# ROV_Power_V2_0.net
KiCad netlist of a schematic drawn in Altium Designer
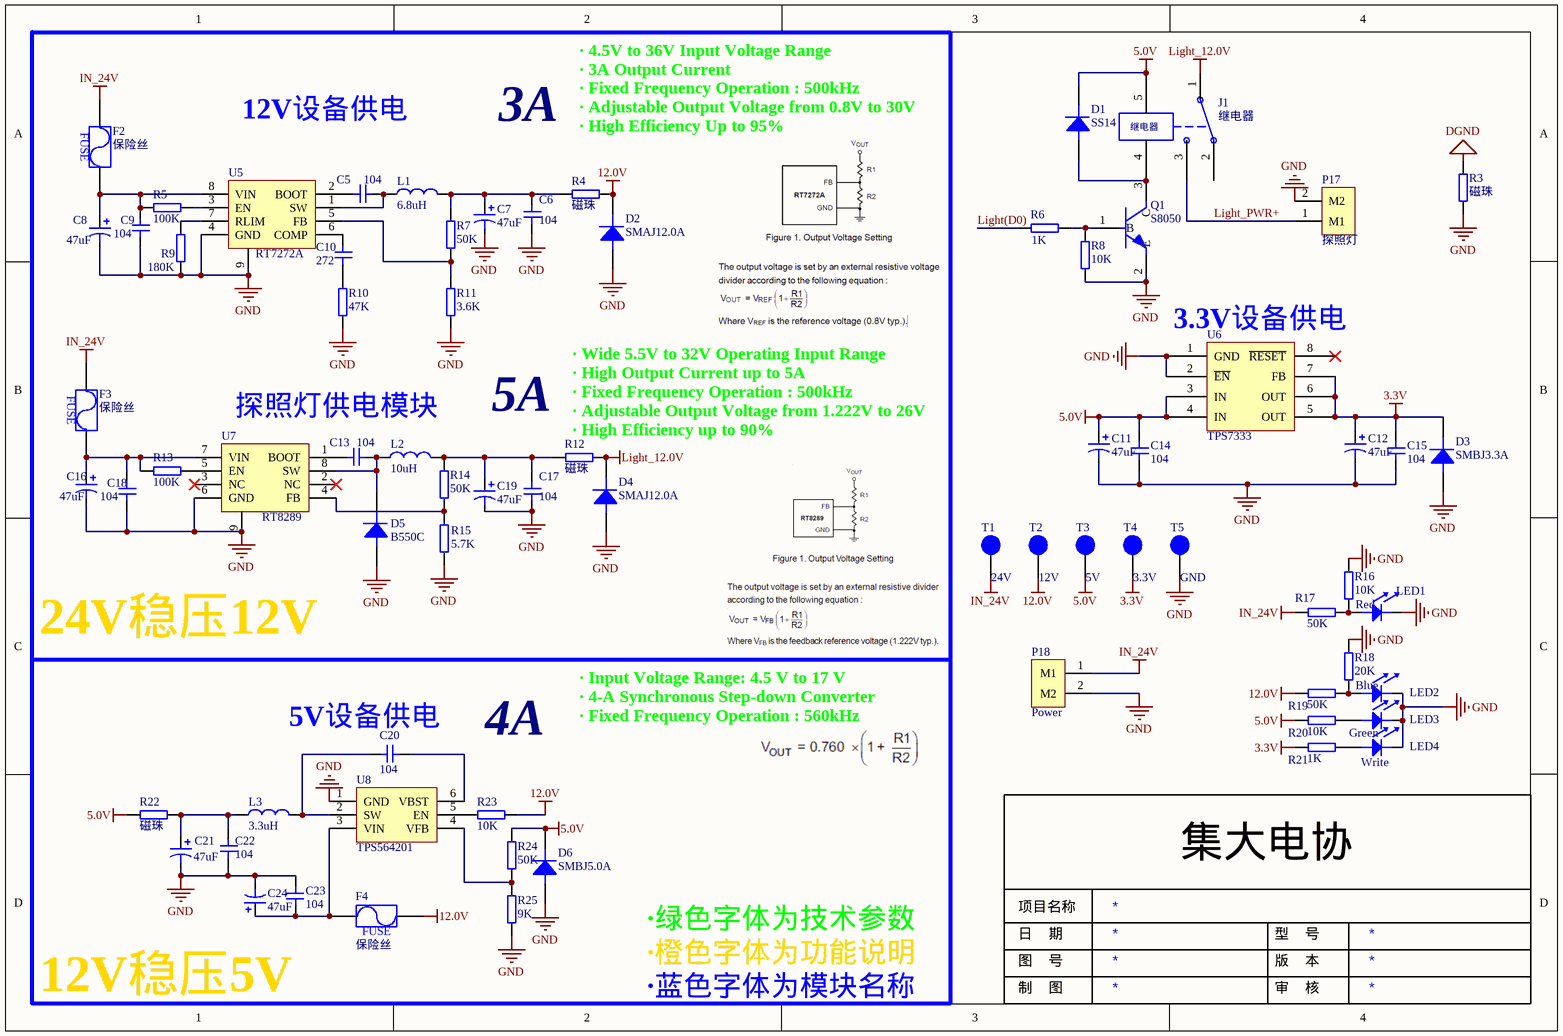
[diagram p0: ROV_Power V2.0.SchDoc]

(export (version "E")
  (design (tool "Eeschema 10.0.6"))
  (components
    (comp (ref "C5")
      (value "104")
      (footprint "0805C")
      (description "无极贴片电容")
      (libsource (lib "集大电协1.2") (part "Cap1"))
    )
    (comp (ref "C6")
      (value "104")
      (footprint "0805C")
      (description "无极贴片电容")
      (libsource (lib "集大电协1.2") (part "Cap1"))
    )
    (comp (ref "C7")
      (value "47uF")
      (footprint "TAJ-B")
      (description "极性贴片电容")
      (libsource (lib "集大电协1.2") (part "Pol Cap"))
    )
    (comp (ref "C8")
      (value "47uF")
      (footprint "TAJ-B")
      (description "极性贴片电容")
      (libsource (lib "集大电协1.2") (part "Pol Cap"))
    )
    (comp (ref "C9")
      (value "104")
      (footprint "0805C")
      (description "无极贴片电容")
      (libsource (lib "集大电协1.2") (part "Cap1"))
    )
    (comp (ref "C10")
      (value "272")
      (footprint "0805C")
      (description "无极贴片电容")
      (libsource (lib "集大电协1.2") (part "Cap1"))
    )
    (comp (ref "C11")
      (value "47uF")
      (footprint "TAJ-B")
      (description "极性贴片电容")
      (libsource (lib "集大电协1.2") (part "Pol Cap"))
    )
    (comp (ref "C12")
      (value "47uF")
      (footprint "TAJ-B")
      (description "极性贴片电容")
      (libsource (lib "集大电协1.2") (part "Pol Cap"))
    )
    (comp (ref "C13")
      (value "104")
      (footprint "0805C")
      (description "无极贴片电容")
      (libsource (lib "集大电协1.2") (part "Cap1"))
    )
    (comp (ref "C14")
      (value "104")
      (footprint "0805C")
      (description "无极贴片电容")
      (libsource (lib "集大电协1.2") (part "Cap1"))
    )
    (comp (ref "C15")
      (value "104")
      (footprint "0805C")
      (description "无极贴片电容")
      (libsource (lib "集大电协1.2") (part "Cap1"))
    )
    (comp (ref "C16")
      (value "47uF")
      (footprint "TAJ-B")
      (description "极性贴片电容")
      (libsource (lib "集大电协1.2") (part "Pol Cap"))
    )
    (comp (ref "C17")
      (value "104")
      (footprint "0805C")
      (description "无极贴片电容")
      (libsource (lib "集大电协1.2") (part "Cap1"))
    )
    (comp (ref "C18")
      (value "104")
      (footprint "0805C")
      (description "无极贴片电容")
      (libsource (lib "集大电协1.2") (part "Cap1"))
    )
    (comp (ref "C19")
      (value "47uF")
      (footprint "TAJ-B")
      (description "极性贴片电容")
      (libsource (lib "集大电协1.2") (part "Pol Cap"))
    )
    (comp (ref "C20")
      (value "104")
      (footprint "0805C")
      (description "无极贴片电容")
      (libsource (lib "集大电协1.2") (part "Cap1"))
    )
    (comp (ref "C21")
      (value "47uF")
      (footprint "TAJ-B")
      (description "极性贴片电容")
      (libsource (lib "集大电协1.2") (part "Pol Cap"))
    )
    (comp (ref "C22")
      (value "104")
      (footprint "0805C")
      (description "无极贴片电容")
      (libsource (lib "集大电协1.2") (part "Cap1"))
    )
    (comp (ref "C23")
      (value "104")
      (footprint "0805C")
      (description "无极贴片电容")
      (libsource (lib "集大电协1.2") (part "Cap1"))
    )
    (comp (ref "C24")
      (value "47uF")
      (footprint "TAJ-B")
      (description "极性贴片电容")
      (libsource (lib "集大电协1.2") (part "Pol Cap"))
    )
    (comp (ref "D1")
      (value "SS14")
      (footprint "SMA/DO-214AC")
      (description "二极管")
      (libsource (lib "集大电协1.1.0") (part "Diode"))
    )
    (comp (ref "D2")
      (value "SMAJ12.0A")
      (footprint "SMBJ")
      (description "二极管")
      (libsource (lib "集大电协1.2") (part "Diode"))
    )
    (comp (ref "D3")
      (value "SMBJ3.3A")
      (footprint "SMBJ")
      (description "二极管")
      (libsource (lib "集大电协1.2") (part "Diode"))
    )
    (comp (ref "D4")
      (value "SMAJ12.0A")
      (footprint "SMBJ")
      (description "二极管")
      (libsource (lib "集大电协1.2") (part "Diode"))
    )
    (comp (ref "D5")
      (value "B550C")
      (footprint "SMBJ")
      (description "二极管")
      (libsource (lib "集大电协1.2") (part "Diode"))
    )
    (comp (ref "D6")
      (value "SMBJ5.0A")
      (footprint "SMBJ")
      (description "二极管")
      (libsource (lib "集大电协1.2") (part "Diode"))
    )
    (comp (ref "F2") (value "保险丝") (footprint "1812") (libsource (lib "集大电协1.2") (part "Fuse")))
    (comp (ref "F3") (value "保险丝") (footprint "1812") (libsource (lib "集大电协1.2") (part "Fuse")))
    (comp (ref "F4") (value "保险丝") (footprint "1812") (libsource (lib "集大电协1.2") (part "Fuse")))
    (comp (ref "J1") (value "继电器") (footprint "继电器(小型)") (libsource (lib "集大电协1.1.0") (part "继电器")))
    (comp (ref "L1")
      (value "6.8uH")
      (footprint "电感")
      (description "电感")
      (libsource (lib "集大电协1.2") (part "L"))
    )
    (comp (ref "L2")
      (value "10uH")
      (footprint "电感")
      (description "电感")
      (libsource (lib "集大电协1.2") (part "L"))
    )
    (comp (ref "L3")
      (value "3.3uH")
      (footprint "电感")
      (description "电感")
      (libsource (lib "集大电协1.2") (part "L"))
    )
    (comp (ref "LED1")
      (value "Red")
      (footprint "0805LED(GREEN)")
      (description "发光二极管")
      (libsource (lib "集大电协1.2") (part "LED"))
    )
    (comp (ref "LED2")
      (value "Blue")
      (footprint "0805LED(RED)")
      (description "发光二极管")
      (libsource (lib "集大电协1.2") (part "LED"))
    )
    (comp (ref "LED3")
      (value "Green")
      (footprint "0805LED(RED)")
      (description "发光二极管")
      (libsource (lib "集大电协1.2") (part "LED"))
    )
    (comp (ref "LED4")
      (value "Write")
      (footprint "0805LED(RED)")
      (description "发光二极管")
      (libsource (lib "集大电协1.2") (part "LED"))
    )
    (comp (ref "P17")
      (value "探照灯")
      (footprint "KF128-2P")
      (description "2PIN")
      (libsource (lib "集大电协1.2") (part "接线端子-2PIN"))
    )
    (comp (ref "P18")
      (value "Power")
      (footprint "XT60-F")
      (description "2PIN")
      (libsource (lib "") (part "接线端子-2PIN_1"))
    )
    (comp (ref "Q1")
      (value "S8050")
      (footprint "SOT-23")
      (description "NPN三极管")
      (libsource (lib "集大电协1.1.0") (part "NPN"))
    )
    (comp (ref "R3")
      (value "磁珠")
      (footprint "1210R")
      (description "电阻")
      (libsource (lib "集大电协1.2") (part "Res"))
    )
    (comp (ref "R4")
      (value "磁珠")
      (footprint "1210R")
      (description "电阻")
      (libsource (lib "集大电协1.2") (part "Res"))
    )
    (comp (ref "R5")
      (value "100K")
      (footprint "0805R")
      (description "电阻")
      (libsource (lib "集大电协1.2") (part "Res"))
    )
    (comp (ref "R6")
      (value "1K")
      (footprint "0805R")
      (description "电阻")
      (libsource (lib "集大电协1.1.0") (part "Res"))
    )
    (comp (ref "R7")
      (value "50K")
      (footprint "0805R")
      (description "电阻")
      (libsource (lib "集大电协1.2") (part "Res"))
    )
    (comp (ref "R8")
      (value "10K")
      (footprint "0805R")
      (description "电阻")
      (libsource (lib "集大电协1.2") (part "Res"))
    )
    (comp (ref "R9")
      (value "180K")
      (footprint "0805R")
      (description "电阻")
      (libsource (lib "集大电协1.2") (part "Res"))
    )
    (comp (ref "R10")
      (value "47K")
      (footprint "0805R")
      (description "电阻")
      (libsource (lib "集大电协1.2") (part "Res"))
    )
    (comp (ref "R11")
      (value "3.6K")
      (footprint "0805R")
      (description "电阻")
      (libsource (lib "集大电协1.2") (part "Res"))
    )
    (comp (ref "R12")
      (value "磁珠")
      (footprint "1210R")
      (description "电阻")
      (libsource (lib "集大电协1.2") (part "Res"))
    )
    (comp (ref "R13")
      (value "100K")
      (footprint "0805R")
      (description "电阻")
      (libsource (lib "集大电协1.2") (part "Res"))
    )
    (comp (ref "R14")
      (value "50K")
      (footprint "0805R")
      (description "电阻")
      (libsource (lib "集大电协1.2") (part "Res"))
    )
    (comp (ref "R15")
      (value "5.7K")
      (footprint "0805R")
      (description "电阻")
      (libsource (lib "集大电协1.2") (part "Res"))
    )
    (comp (ref "R16")
      (value "10K")
      (footprint "0805R")
      (description "电阻")
      (libsource (lib "集大电协1.2") (part "Res"))
    )
    (comp (ref "R17")
      (value "50K")
      (footprint "0805R")
      (description "电阻")
      (libsource (lib "集大电协1.2") (part "Res"))
    )
    (comp (ref "R18")
      (value "20K")
      (footprint "0805R")
      (description "电阻")
      (libsource (lib "集大电协1.2") (part "Res"))
    )
    (comp (ref "R19")
      (value "50K")
      (footprint "0805R")
      (description "电阻")
      (libsource (lib "集大电协1.2") (part "Res"))
    )
    (comp (ref "R20")
      (value "10K")
      (footprint "0805R")
      (description "电阻")
      (libsource (lib "集大电协1.2") (part "Res"))
    )
    (comp (ref "R21")
      (value "1K")
      (footprint "0805R")
      (description "电阻")
      (libsource (lib "集大电协1.2") (part "Res"))
    )
    (comp (ref "R22")
      (value "磁珠")
      (footprint "1210R")
      (description "电阻")
      (libsource (lib "集大电协1.2") (part "Res"))
    )
    (comp (ref "R23")
      (value "10K")
      (footprint "0805R")
      (description "电阻")
      (libsource (lib "集大电协1.2") (part "Res"))
    )
    (comp (ref "R24")
      (value "50K")
      (footprint "0805R")
      (description "电阻")
      (libsource (lib "集大电协1.2") (part "Res"))
    )
    (comp (ref "R25")
      (value "9K")
      (footprint "0805R")
      (description "电阻")
      (libsource (lib "集大电协1.2") (part "Res"))
    )
    (comp (ref "T1")
      (value "24V")
      (footprint "测试点(实心)")
      (description "测试点")
      (libsource (lib "集大电协1.2") (part "测试点"))
    )
    (comp (ref "T2")
      (value "12V")
      (footprint "测试点(实心)")
      (description "测试点")
      (libsource (lib "集大电协1.2") (part "测试点"))
    )
    (comp (ref "T3")
      (value "5V")
      (footprint "测试点(实心)")
      (description "测试点")
      (libsource (lib "集大电协1.2") (part "测试点"))
    )
    (comp (ref "T4")
      (value "3.3V")
      (footprint "测试点(实心)")
      (description "测试点")
      (libsource (lib "集大电协1.2") (part "测试点"))
    )
    (comp (ref "T5")
      (value "GND")
      (footprint "测试点(实心)")
      (description "测试点")
      (libsource (lib "集大电协1.2") (part "测试点"))
    )
    (comp (ref "U5") (value "RT7272A") (footprint "SOP8-Pad") (libsource (lib "集大电协1.2") (part "RT7272A")))
    (comp (ref "U6")
      (value "TPS7333")
      (footprint "SOP-8")
      (description "3.3V电源芯片")
      (libsource (lib "集大电协1.2") (part "TPS7333"))
    )
    (comp (ref "U7") (value "RT8289") (footprint "SOP8-Pad") (libsource (lib "集大电协1.2") (part "RT8289")))
    (comp (ref "U8") (value "TPS564201") (footprint "SOT23-6") (libsource (lib "集大电协1.2") (part "TPS564201")))
  )
  (nets
    (net (code "1") (name "/Light(D0)") (class "Default")
      (node (ref "R6") (pin "2") (pinfunction "2_2") (pintype "passive"))
    )
    (net (code "2") (name "/Light_PWR+") (class "Default")
      (node (ref "J1") (pin "3") (pinfunction "3_3") (pintype "passive"))
      (node (ref "P17") (pin "1") (pinfunction "M1_1") (pintype "passive"))
    )
    (net (code "3") (name "3.3V") (class "Default")
      (node (ref "C12") (pin "1") (pinfunction "1_1") (pintype "passive"))
      (node (ref "C15") (pin "2") (pinfunction "2_2") (pintype "passive"))
      (node (ref "D3") (pin "2") (pinfunction "2_2") (pintype "passive"))
      (node (ref "R21") (pin "1") (pinfunction "1_1") (pintype "passive"))
      (node (ref "T4") (pin "1") (pinfunction "1_1") (pintype "passive"))
      (node (ref "U6") (pin "5") (pinfunction "OUT_5") (pintype "passive"))
      (node (ref "U6") (pin "6") (pinfunction "OUT_6") (pintype "passive"))
      (node (ref "U6") (pin "7") (pinfunction "FB_7") (pintype "passive"))
    )
    (net (code "4") (name "5.0V") (class "Default")
      (node (ref "C11") (pin "1") (pinfunction "1_1") (pintype "passive"))
      (node (ref "C14") (pin "2") (pinfunction "2_2") (pintype "passive"))
      (node (ref "D1") (pin "2") (pinfunction "2_2") (pintype "passive"))
      (node (ref "D6") (pin "2") (pinfunction "2_2") (pintype "passive"))
      (node (ref "J1") (pin "5") (pinfunction "5_5") (pintype "passive"))
      (node (ref "R20") (pin "1") (pinfunction "1_1") (pintype "passive"))
      (node (ref "R22") (pin "2") (pinfunction "2_2") (pintype "passive"))
      (node (ref "R24") (pin "1") (pinfunction "1_1") (pintype "passive"))
      (node (ref "T3") (pin "1") (pinfunction "1_1") (pintype "passive"))
      (node (ref "U6") (pin "3") (pinfunction "IN_3") (pintype "passive"))
      (node (ref "U6") (pin "4") (pinfunction "IN_4") (pintype "passive"))
    )
    (net (code "5") (name "12.0V") (class "Default")
      (node (ref "D2") (pin "2") (pinfunction "2_2") (pintype "passive"))
      (node (ref "F4") (pin "2") (pinfunction "2_2") (pintype "passive"))
      (node (ref "R19") (pin "1") (pinfunction "1_1") (pintype "passive"))
      (node (ref "R23") (pin "1") (pinfunction "1_1") (pintype "passive"))
      (node (ref "R4") (pin "1") (pinfunction "1_1") (pintype "passive"))
      (node (ref "T2") (pin "1") (pinfunction "1_1") (pintype "passive"))
    )
    (net (code "6") (name "DGND") (class "Default")
      (node (ref "R3") (pin "2") (pinfunction "2_2") (pintype "passive"))
    )
    (net (code "7") (name "GND") (class "Default")
      (node (ref "C11") (pin "2") (pinfunction "2_2") (pintype "passive"))
      (node (ref "C12") (pin "2") (pinfunction "2_2") (pintype "passive"))
      (node (ref "C14") (pin "1") (pinfunction "1_1") (pintype "passive"))
      (node (ref "C15") (pin "1") (pinfunction "1_1") (pintype "passive"))
      (node (ref "C16") (pin "2") (pinfunction "2_2") (pintype "passive"))
      (node (ref "C17") (pin "1") (pinfunction "1_1") (pintype "passive"))
      (node (ref "C18") (pin "1") (pinfunction "1_1") (pintype "passive"))
      (node (ref "C19") (pin "2") (pinfunction "2_2") (pintype "passive"))
      (node (ref "C21") (pin "2") (pinfunction "2_2") (pintype "passive"))
      (node (ref "C22") (pin "1") (pinfunction "1_1") (pintype "passive"))
      (node (ref "C23") (pin "1") (pinfunction "1_1") (pintype "passive"))
      (node (ref "C24") (pin "2") (pinfunction "2_2") (pintype "passive"))
      (node (ref "C6") (pin "1") (pinfunction "1_1") (pintype "passive"))
      (node (ref "C7") (pin "2") (pinfunction "2_2") (pintype "passive"))
      (node (ref "C8") (pin "2") (pinfunction "2_2") (pintype "passive"))
      (node (ref "C9") (pin "1") (pinfunction "1_1") (pintype "passive"))
      (node (ref "D2") (pin "1") (pintype "passive"))
      (node (ref "D3") (pin "1") (pintype "passive"))
      (node (ref "D4") (pin "1") (pintype "passive"))
      (node (ref "D5") (pin "1") (pintype "passive"))
      (node (ref "D6") (pin "1") (pintype "passive"))
      (node (ref "LED1") (pin "2") (pinfunction "2_2") (pintype "passive"))
      (node (ref "LED2") (pin "2") (pinfunction "2_2") (pintype "passive"))
      (node (ref "LED3") (pin "2") (pinfunction "2_2") (pintype "passive"))
      (node (ref "LED4") (pin "2") (pinfunction "2_2") (pintype "passive"))
      (node (ref "P17") (pin "2") (pinfunction "M2_2") (pintype "passive"))
      (node (ref "P18") (pin "2") (pinfunction "M2_2") (pintype "passive"))
      (node (ref "Q1") (pin "2") (pinfunction "E_2") (pintype "passive"))
      (node (ref "R10") (pin "1") (pinfunction "1_1") (pintype "passive"))
      (node (ref "R11") (pin "1") (pinfunction "1_1") (pintype "passive"))
      (node (ref "R15") (pin "1") (pinfunction "1_1") (pintype "passive"))
      (node (ref "R16") (pin "2") (pinfunction "2_2") (pintype "passive"))
      (node (ref "R18") (pin "2") (pinfunction "2_2") (pintype "passive"))
      (node (ref "R25") (pin "1") (pinfunction "1_1") (pintype "passive"))
      (node (ref "R3") (pin "1") (pinfunction "1_1") (pintype "passive"))
      (node (ref "R8") (pin "1") (pinfunction "1_1") (pintype "passive"))
      (node (ref "R9") (pin "1") (pinfunction "1_1") (pintype "passive"))
      (node (ref "T5") (pin "1") (pinfunction "1_1") (pintype "passive"))
      (node (ref "U5") (pin "4") (pinfunction "GND_4") (pintype "passive"))
      (node (ref "U5") (pin "9") (pinfunction "GND_9") (pintype "passive"))
      (node (ref "U6") (pin "1") (pinfunction "GND_1") (pintype "passive"))
      (node (ref "U6") (pin "2") (pinfunction "~{EN}_2") (pintype "power_in"))
      (node (ref "U7") (pin "6") (pinfunction "GND_6") (pintype "passive"))
      (node (ref "U7") (pin "9") (pinfunction "GND_9") (pintype "passive"))
      (node (ref "U8") (pin "1") (pinfunction "GND_1") (pintype "passive"))
    )
    (net (code "8") (name "IN_24V") (class "Default")
      (node (ref "F2") (pin "1") (pinfunction "1_1") (pintype "passive"))
      (node (ref "F3") (pin "1") (pinfunction "1_1") (pintype "passive"))
      (node (ref "P18") (pin "1") (pinfunction "M1_1") (pintype "passive"))
      (node (ref "R17") (pin "1") (pinfunction "1_1") (pintype "passive"))
      (node (ref "T1") (pin "1") (pinfunction "1_1") (pintype "passive"))
    )
    (net (code "9") (name "Light_12.0V") (class "Default")
      (node (ref "D4") (pin "2") (pinfunction "2_2") (pintype "passive"))
      (node (ref "J1") (pin "1") (pinfunction "1_1") (pintype "passive"))
      (node (ref "R12") (pin "1") (pinfunction "1_1") (pintype "passive"))
    )
    (net (code "10") (name "Net-(C6-Pad2)") (class "Default")
      (node (ref "C6") (pin "2") (pinfunction "2_2") (pintype "passive"))
      (node (ref "C7") (pin "1") (pinfunction "1_1") (pintype "passive"))
      (node (ref "L1") (pin "2") (pinfunction "2_2") (pintype "passive"))
      (node (ref "R4") (pin "2") (pinfunction "2_2") (pintype "passive"))
      (node (ref "R7") (pin "1") (pinfunction "1_1") (pintype "passive"))
    )
    (net (code "11") (name "Net-(C10-Pad1)") (class "Default")
      (node (ref "C10") (pin "1") (pinfunction "1_1") (pintype "passive"))
      (node (ref "R10") (pin "2") (pinfunction "2_2") (pintype "passive"))
    )
    (net (code "12") (name "Net-(C17-Pad2)") (class "Default")
      (node (ref "C17") (pin "2") (pinfunction "2_2") (pintype "passive"))
      (node (ref "C19") (pin "1") (pinfunction "1_1") (pintype "passive"))
      (node (ref "L2") (pin "2") (pinfunction "2_2") (pintype "passive"))
      (node (ref "R12") (pin "2") (pinfunction "2_2") (pintype "passive"))
      (node (ref "R14") (pin "1") (pinfunction "1_1") (pintype "passive"))
    )
    (net (code "13") (name "Net-(C21-Pad1)") (class "Default")
      (node (ref "C21") (pin "1") (pinfunction "1_1") (pintype "passive"))
      (node (ref "C22") (pin "2") (pinfunction "2_2") (pintype "passive"))
      (node (ref "L3") (pin "1") (pinfunction "1_1") (pintype "passive"))
      (node (ref "R22") (pin "1") (pinfunction "1_1") (pintype "passive"))
    )
    (net (code "14") (name "Net-(LED1-Pad1)") (class "Default")
      (node (ref "LED1") (pin "1") (pintype "passive"))
      (node (ref "R16") (pin "1") (pinfunction "1_1") (pintype "passive"))
      (node (ref "R17") (pin "2") (pinfunction "2_2") (pintype "passive"))
    )
    (net (code "15") (name "Net-(LED2-Pad1)") (class "Default")
      (node (ref "LED2") (pin "1") (pintype "passive"))
      (node (ref "R18") (pin "1") (pinfunction "1_1") (pintype "passive"))
      (node (ref "R19") (pin "2") (pinfunction "2_2") (pintype "passive"))
    )
    (net (code "16") (name "Net-(LED3-Pad1)") (class "Default")
      (node (ref "LED3") (pin "1") (pintype "passive"))
      (node (ref "R20") (pin "2") (pinfunction "2_2") (pintype "passive"))
    )
    (net (code "17") (name "Net-(LED4-Pad1)") (class "Default")
      (node (ref "LED4") (pin "1") (pintype "passive"))
      (node (ref "R21") (pin "2") (pinfunction "2_2") (pintype "passive"))
    )
    (net (code "18") (name "Net-(Q1-B)") (class "Default")
      (node (ref "Q1") (pin "1") (pinfunction "B_1") (pintype "passive"))
      (node (ref "R6") (pin "1") (pinfunction "1_1") (pintype "passive"))
      (node (ref "R8") (pin "2") (pinfunction "2_2") (pintype "passive"))
    )
    (net (code "19") (name "Net-(Q1-C)") (class "Default")
      (node (ref "D1") (pin "1") (pintype "passive"))
      (node (ref "J1") (pin "4") (pinfunction "4_4") (pintype "passive"))
      (node (ref "Q1") (pin "3") (pinfunction "C_3") (pintype "passive"))
    )
    (net (code "20") (name "Net-(U5-BOOT)") (class "Default")
      (node (ref "C5") (pin "2") (pinfunction "2_2") (pintype "passive"))
      (node (ref "U5") (pin "2") (pinfunction "BOOT_2") (pintype "passive"))
    )
    (net (code "21") (name "Net-(U5-COMP)") (class "Default")
      (node (ref "C10") (pin "2") (pinfunction "2_2") (pintype "passive"))
      (node (ref "U5") (pin "6") (pinfunction "COMP_6") (pintype "passive"))
    )
    (net (code "22") (name "Net-(U5-EN)") (class "Default")
      (node (ref "R5") (pin "2") (pinfunction "2_2") (pintype "passive"))
      (node (ref "U5") (pin "3") (pinfunction "EN_3") (pintype "passive"))
    )
    (net (code "23") (name "Net-(U5-FB)") (class "Default")
      (node (ref "R11") (pin "2") (pinfunction "2_2") (pintype "passive"))
      (node (ref "R7") (pin "2") (pinfunction "2_2") (pintype "passive"))
      (node (ref "U5") (pin "5") (pinfunction "FB_5") (pintype "passive"))
    )
    (net (code "24") (name "Net-(U5-RLIM)") (class "Default")
      (node (ref "R9") (pin "2") (pinfunction "2_2") (pintype "passive"))
      (node (ref "U5") (pin "7") (pinfunction "RLIM_7") (pintype "passive"))
    )
    (net (code "25") (name "Net-(U5-SW)") (class "Default")
      (node (ref "C5") (pin "1") (pinfunction "1_1") (pintype "passive"))
      (node (ref "L1") (pin "1") (pinfunction "1_1") (pintype "passive"))
      (node (ref "U5") (pin "1") (pinfunction "SW_1") (pintype "passive"))
    )
    (net (code "26") (name "Net-(U5-VIN)") (class "Default")
      (node (ref "C8") (pin "1") (pinfunction "1_1") (pintype "passive"))
      (node (ref "C9") (pin "2") (pinfunction "2_2") (pintype "passive"))
      (node (ref "F2") (pin "2") (pinfunction "2_2") (pintype "passive"))
      (node (ref "R5") (pin "1") (pinfunction "1_1") (pintype "passive"))
      (node (ref "U5") (pin "8") (pinfunction "VIN_8") (pintype "passive"))
    )
    (net (code "27") (name "Net-(U7-BOOT)") (class "Default")
      (node (ref "C13") (pin "2") (pinfunction "2_2") (pintype "passive"))
      (node (ref "U7") (pin "1") (pinfunction "BOOT_1") (pintype "passive"))
    )
    (net (code "28") (name "Net-(U7-EN)") (class "Default")
      (node (ref "R13") (pin "2") (pinfunction "2_2") (pintype "passive"))
      (node (ref "U7") (pin "5") (pinfunction "EN_5") (pintype "passive"))
    )
    (net (code "29") (name "Net-(U7-FB)") (class "Default")
      (node (ref "R14") (pin "2") (pinfunction "2_2") (pintype "passive"))
      (node (ref "R15") (pin "2") (pinfunction "2_2") (pintype "passive"))
      (node (ref "U7") (pin "4") (pinfunction "FB_4") (pintype "passive"))
    )
    (net (code "30") (name "Net-(U7-SW)") (class "Default")
      (node (ref "C13") (pin "1") (pinfunction "1_1") (pintype "passive"))
      (node (ref "D5") (pin "2") (pinfunction "2_2") (pintype "passive"))
      (node (ref "L2") (pin "1") (pinfunction "1_1") (pintype "passive"))
      (node (ref "U7") (pin "8") (pinfunction "SW_8") (pintype "passive"))
    )
    (net (code "31") (name "Net-(U7-VIN)") (class "Default")
      (node (ref "C16") (pin "1") (pinfunction "1_1") (pintype "passive"))
      (node (ref "C18") (pin "2") (pinfunction "2_2") (pintype "passive"))
      (node (ref "F3") (pin "2") (pinfunction "2_2") (pintype "passive"))
      (node (ref "R13") (pin "1") (pinfunction "1_1") (pintype "passive"))
      (node (ref "U7") (pin "7") (pinfunction "VIN_7") (pintype "passive"))
    )
    (net (code "32") (name "Net-(U8-EN)") (class "Default")
      (node (ref "R23") (pin "2") (pinfunction "2_2") (pintype "passive"))
      (node (ref "U8") (pin "5") (pinfunction "EN_5") (pintype "passive"))
    )
    (net (code "33") (name "Net-(U8-SW)") (class "Default")
      (node (ref "C20") (pin "2") (pinfunction "2_2") (pintype "passive"))
      (node (ref "L3") (pin "2") (pinfunction "2_2") (pintype "passive"))
      (node (ref "U8") (pin "2") (pinfunction "SW_2") (pintype "passive"))
    )
    (net (code "34") (name "Net-(U8-VBST)") (class "Default")
      (node (ref "C20") (pin "1") (pinfunction "1_1") (pintype "passive"))
      (node (ref "U8") (pin "6") (pinfunction "VBST_6") (pintype "passive"))
    )
    (net (code "35") (name "Net-(U8-VFB)") (class "Default")
      (node (ref "R24") (pin "2") (pinfunction "2_2") (pintype "passive"))
      (node (ref "R25") (pin "2") (pinfunction "2_2") (pintype "passive"))
      (node (ref "U8") (pin "4") (pinfunction "VFB_4") (pintype "passive"))
    )
    (net (code "36") (name "Net-(U8-VIN)") (class "Default")
      (node (ref "C23") (pin "2") (pinfunction "2_2") (pintype "passive"))
      (node (ref "C24") (pin "1") (pinfunction "1_1") (pintype "passive"))
      (node (ref "F4") (pin "1") (pinfunction "1_1") (pintype "passive"))
      (node (ref "U8") (pin "3") (pinfunction "VIN_3") (pintype "passive"))
    )
    (net (code "37") (name "unconnected-(J1-Pad2)") (class "Default")
      (node (ref "J1") (pin "2") (pinfunction "2_2") (pintype "passive"))
    )
    (net (code "38") (name "unconnected-(U6-~{RESET}-Pad8)") (class "Default")
      (node (ref "U6") (pin "8") (pinfunction "~{RESET}_8") (pintype "passive+no_connect"))
    )
    (net (code "39") (name "unconnected-(U7-NC-Pad2)") (class "Default")
      (node (ref "U7") (pin "2") (pinfunction "NC_2") (pintype "passive+no_connect"))
    )
    (net (code "40") (name "unconnected-(U7-NC-Pad3)") (class "Default")
      (node (ref "U7") (pin "3") (pinfunction "NC_3") (pintype "passive+no_connect"))
    )
  )
)
